# Emergency_Thermal_Shutdown.net
KiCad netlist of a schematic drawn in Altium Designer
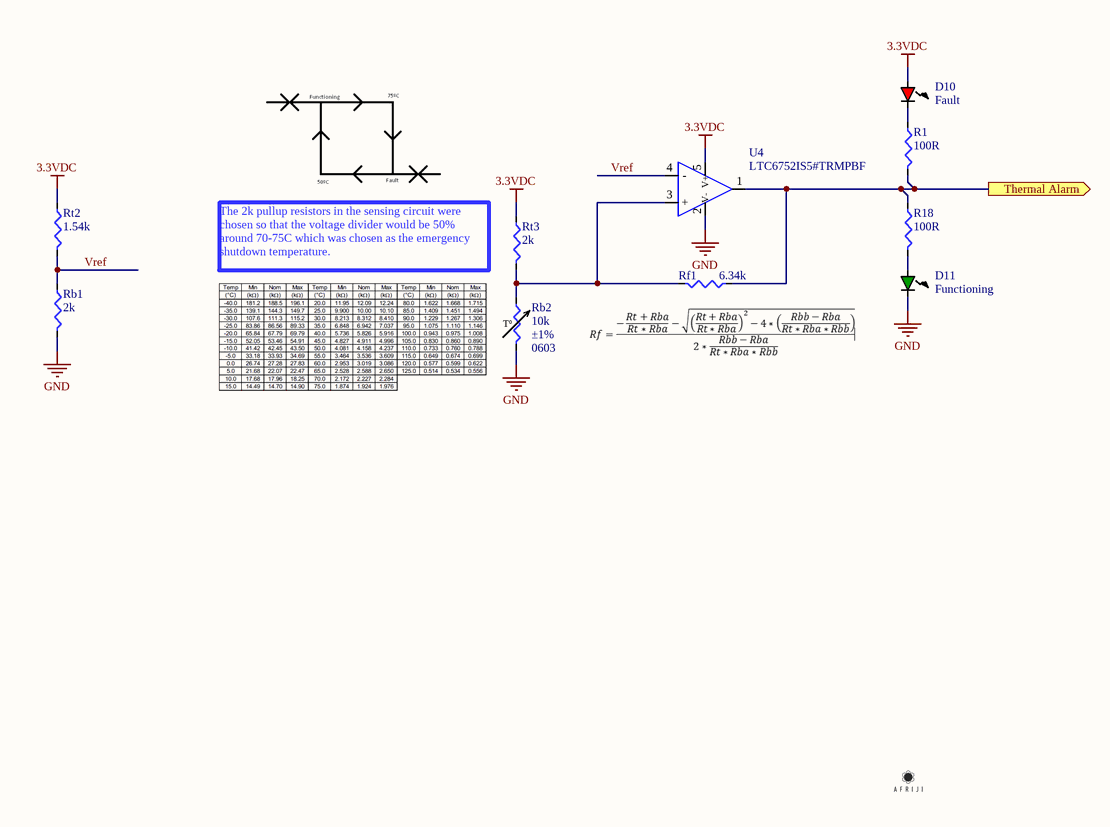
[diagram p0: Emergency Thermal Shutdown.SchDoc]

(export (version "E")
  (design (tool "Eeschema 10.0.6"))
  (components
    (comp (ref "D10")
      (value "Fault")
      (footprint "LED - 1206 Red")
      (fields
        (field (name "MANUFACTURER") "Kingbright")
        (field (name "MANUFACTURER PART NUMBER") "APT3216SRCPRV")
      )
      (libsource (lib "Personal Library") (part "Red LED 1206"))
    )
    (comp (ref "D11")
      (value "Functioning")
      (footprint "LED - 1206 Green")
      (fields
        (field (name "MANUFACTURER") "Kingbright")
        (field (name "MANUFACTURER PART NUMBER") "APL3015SGC-F01")
      )
      (libsource (lib "Personal Library") (part "Green LED 1206"))
    )
    (comp (ref "R1")
      (value "100R 0603 1%")
      (footprint "R0603")
      (description "1/8W")
      (fields
        (field (name "MANUFACTURER") "Yageo")
        (field (name "MANUFACTURER PART NUMBER") "RC0603FR-07100RL")
        (field (name "RESISTANCE (OHMS)") "100R")
      )
      (libsource (lib "Personal Library") (part "100R 0603 1%"))
    )
    (comp (ref "R18")
      (value "100R 0603 1%")
      (footprint "R0603")
      (description "1/8W")
      (fields
        (field (name "MANUFACTURER") "Yageo")
        (field (name "MANUFACTURER PART NUMBER") "RC0603FR-07100RL")
        (field (name "RESISTANCE (OHMS)") "100R")
      )
      (libsource (lib "Personal Library") (part "100R 0603 1%"))
    )
    (comp (ref "Rb1")
      (value "2k 0603 1%")
      (footprint "R0603")
      (fields
        (field (name "MANUFACTURER") "Panasonic Electronic Components")
        (field (name "MANUFACTURER PART NUMBER") "ERJ-3EKF2001V")
        (field (name "TOLERANCE") "±1%")
        (field (name "RESISTANCE (OHMS)") "2k")
      )
      (libsource (lib "Personal Library") (part "2k 0603 1%"))
    )
    (comp (ref "Rb2")
      (value "Thermistor 10k Type J SMT")
      (description "Resistor")
      (fields
        (field (name "MANUFACTURER") "TDK Corporation")
        (field (name "MANUFACTURER PART NUMBER") "NTCG163JF103FTDS")
        (field (name "RESISTANCE IN OHMS @ 25°C") "10k")
        (field (name "RESISTANCE TOLERANCE") "±1%")
        (field (name "PACKAGE / CASE") "0603")
      )
      (libsource (lib "Local Library") (part "Thermistor 10k Type J SMT"))
    )
    (comp (ref "Rf1")
      (value "6.34k 0603 1%")
      (footprint "R0603")
      (fields
        (field (name "MANUFACTURER") "Yageo")
        (field (name "MANUFACTURER PART NUMBER") "RC0603FR-076K34L")
        (field (name "TOLERANCE") "±1%")
        (field (name "RESISTANCE") "6.34k")
      )
      (libsource (lib "Local Library") (part "6.34k 0603 1%"))
    )
    (comp (ref "Rt2")
      (value "1.54k 0603 1%")
      (footprint "R0603")
      (fields
        (field (name "MANUFACTURER") "Yageo")
        (field (name "MANUFACTURER PART NUMBER") "RC0603FR-071K54L")
        (field (name "TOLERANCE") "±1%")
        (field (name "RESISTANCE") "1.54k")
      )
      (libsource (lib "Local Library") (part "1.54k 0603 1%"))
    )
    (comp (ref "Rt3")
      (value "2k 0603 1%")
      (footprint "R0603")
      (fields
        (field (name "MANUFACTURER") "Panasonic Electronic Components")
        (field (name "MANUFACTURER PART NUMBER") "ERJ-3EKF2001V")
        (field (name "TOLERANCE") "±1%")
        (field (name "RESISTANCE (OHMS)") "2k")
      )
      (libsource (lib "Personal Library") (part "2k 0603 1%"))
    )
    (comp (ref "U4")
      (value "Single Comparator LTC6752")
      (fields
        (field (name "MANUFACTURER") "Linear Technology")
        (field (name "MANUFACTURER PART NUMBER") "LTC6752IS5#TRMPBF")
      )
      (libsource (lib "Local Library") (part "Single Comparator LTC6752"))
    )
  )
  (nets
    (net (code "1") (name "/Thermal Alarm") (class "Default")
      (node (ref "R1") (pin "1") (pinfunction "1_1") (pintype "passive"))
      (node (ref "R18") (pin "2") (pinfunction "2_2") (pintype "passive"))
      (node (ref "Rf1") (pin "2") (pinfunction "2_2") (pintype "passive"))
      (node (ref "U4") (pin "1") (pinfunction "Out_1") (pintype "passive"))
    )
    (net (code "2") (name "/Vref") (class "Default")
      (node (ref "Rb1") (pin "2") (pinfunction "2_2") (pintype "passive"))
      (node (ref "Rt2") (pin "1") (pinfunction "1_1") (pintype "passive"))
      (node (ref "U4") (pin "4") (pinfunction "-_4") (pintype "passive"))
    )
    (net (code "3") (name "3.3VDC") (class "Default")
      (node (ref "D10") (pin "1") (pinfunction "1_1") (pintype "passive"))
      (node (ref "Rt2") (pin "2") (pinfunction "2_2") (pintype "passive"))
      (node (ref "Rt3") (pin "2") (pinfunction "2_2") (pintype "passive"))
      (node (ref "U4") (pin "5") (pinfunction "V+_5") (pintype "passive"))
    )
    (net (code "4") (name "GND") (class "Default")
      (node (ref "D11") (pin "2") (pinfunction "2_2") (pintype "passive"))
      (node (ref "Rb1") (pin "1") (pinfunction "1_1") (pintype "passive"))
      (node (ref "Rb2") (pin "2") (pinfunction "2_2") (pintype "passive"))
      (node (ref "U4") (pin "2") (pinfunction "V-_2") (pintype "passive"))
    )
    (net (code "5") (name "Net-(D10-Pad2)") (class "Default")
      (node (ref "D10") (pin "2") (pinfunction "2_2") (pintype "passive"))
      (node (ref "R1") (pin "2") (pinfunction "2_2") (pintype "passive"))
    )
    (net (code "6") (name "Net-(D11-Pad1)") (class "Default")
      (node (ref "D11") (pin "1") (pinfunction "1_1") (pintype "passive"))
      (node (ref "R18") (pin "1") (pinfunction "1_1") (pintype "passive"))
    )
    (net (code "7") (name "Net-(U4-+)") (class "Default")
      (node (ref "Rb2") (pin "1") (pinfunction "1_1") (pintype "passive"))
      (node (ref "Rf1") (pin "1") (pinfunction "1_1") (pintype "passive"))
      (node (ref "Rt3") (pin "1") (pinfunction "1_1") (pintype "passive"))
      (node (ref "U4") (pin "3") (pinfunction "+_3") (pintype "passive"))
    )
  )
)
